# AVR28.net
KiCad netlist of a schematic drawn in EAGLE
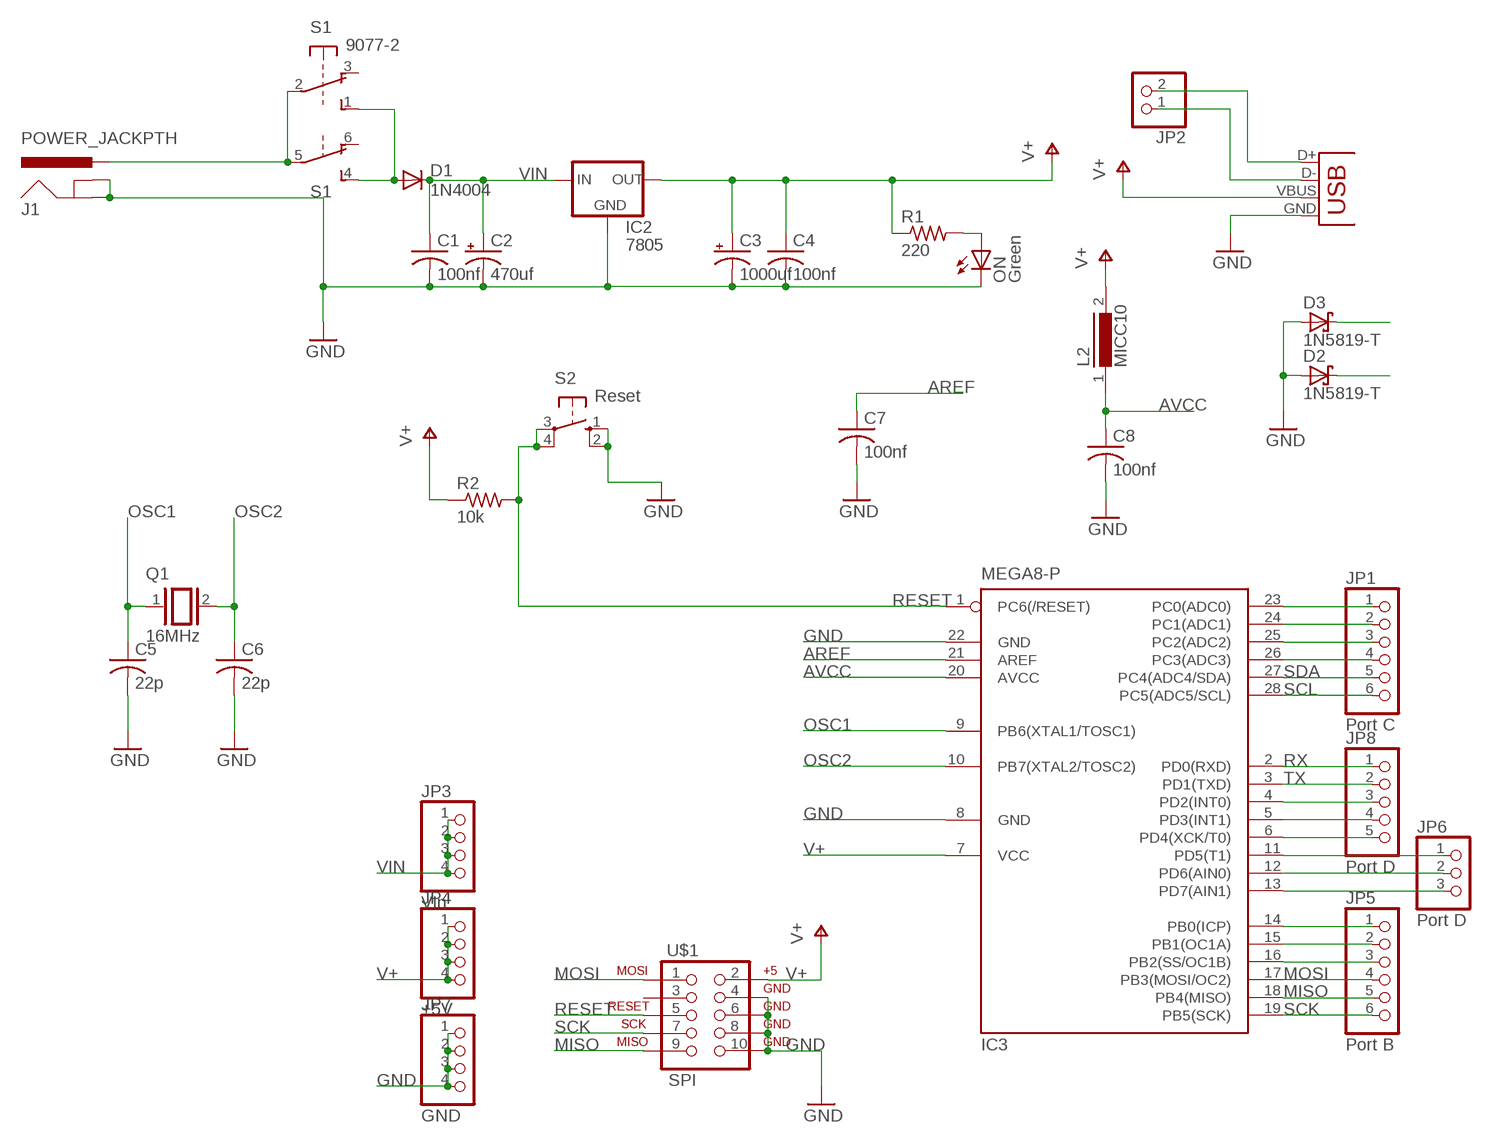
[diagram p0: schematic, sheet 1]

(export (version "E")
  (design (tool "Eeschema 10.0.6"))
  (components
    (comp (ref "C1")
      (value "100nf")
      (footprint "eagle-import:C050-025X075")
      (libsource (lib "eagle-import") (part "C-US050-025X075"))
    )
    (comp (ref "C2")
      (value "470uf")
      (footprint "eagle-import:E3,5-8")
      (libsource (lib "eagle-import") (part "CPOL-USE3.5-8"))
    )
    (comp (ref "C3")
      (value "1000uf")
      (footprint "eagle-import:E3,5-8")
      (libsource (lib "eagle-import") (part "CPOL-USE3.5-8"))
    )
    (comp (ref "C4")
      (value "100nf")
      (footprint "eagle-import:C050-025X075")
      (libsource (lib "eagle-import") (part "C-US050-025X075"))
    )
    (comp (ref "C5")
      (value "22p")
      (footprint "eagle-import:C050-025X075")
      (libsource (lib "eagle-import") (part "C-US050-025X075"))
    )
    (comp (ref "C6")
      (value "22p")
      (footprint "eagle-import:C050-025X075")
      (libsource (lib "eagle-import") (part "C-US050-025X075"))
    )
    (comp (ref "C7")
      (value "100nf")
      (footprint "eagle-import:C050-025X075")
      (libsource (lib "eagle-import") (part "C-US050-025X075"))
    )
    (comp (ref "C8")
      (value "100nf")
      (footprint "eagle-import:C050-025X075")
      (libsource (lib "eagle-import") (part "C-US050-025X075"))
    )
    (comp (ref "D1")
      (value "1N4004")
      (footprint "eagle-import:DO41-10")
      (libsource (lib "eagle-import") (part "1N4004"))
    )
    (comp (ref "D2")
      (value "1N5819-T")
      (footprint "eagle-import:DO41-7.6")
      (libsource (lib "eagle-import") (part "1N5819-T"))
    )
    (comp (ref "D3")
      (value "1N5819-T")
      (footprint "eagle-import:DO41-7.6")
      (libsource (lib "eagle-import") (part "1N5819-T"))
    )
    (comp (ref "IC2")
      (value "7805")
      (footprint "eagle-import:78XXL")
      (libsource (lib "eagle-import") (part "V_REG_78XXSIDE"))
    )
    (comp (ref "IC3")
      (value "MEGA8-P")
      (footprint "eagle-import:DIL28-3")
      (libsource (lib "eagle-import") (part "MEGA8-P"))
    )
    (comp (ref "J1")
      (value "POWER_JACKPTH")
      (footprint "eagle-import:POWER_JACK_PTH")
      (libsource (lib "eagle-import") (part "POWER_JACKPTH"))
    )
    (comp (ref "JP1")
      (value "Port C")
      (footprint "eagle-import:1X06")
      (libsource (lib "eagle-import") (part "PINHD-1X6"))
    )
    (comp (ref "JP2")
      (value "PINHD-1X2")
      (footprint "eagle-import:1X02")
      (libsource (lib "eagle-import") (part "PINHD-1X2"))
    )
    (comp (ref "JP3")
      (value "VIn")
      (footprint "eagle-import:1X04")
      (libsource (lib "eagle-import") (part "PINHD-1X4"))
    )
    (comp (ref "JP4")
      (value "+5V")
      (footprint "eagle-import:1X04")
      (libsource (lib "eagle-import") (part "PINHD-1X4"))
    )
    (comp (ref "JP5")
      (value "Port B")
      (footprint "eagle-import:1X06")
      (libsource (lib "eagle-import") (part "PINHD-1X6"))
    )
    (comp (ref "JP6")
      (value "Port D")
      (footprint "eagle-import:1X03")
      (libsource (lib "eagle-import") (part "PINHD-1X3"))
    )
    (comp (ref "JP7")
      (value "GND")
      (footprint "eagle-import:1X04")
      (libsource (lib "eagle-import") (part "PINHD-1X4"))
    )
    (comp (ref "JP8")
      (value "Port D")
      (footprint "eagle-import:1X05")
      (libsource (lib "eagle-import") (part "PINHD-1X5"))
    )
    (comp (ref "L2")
      (value "MICC10")
      (footprint "eagle-import:MICC10")
      (libsource (lib "eagle-import") (part "MICC10"))
    )
    (comp (ref "ON")
      (value "Green")
      (footprint "eagle-import:LED3MM")
      (libsource (lib "eagle-import") (part "LED3MM"))
    )
    (comp (ref "Q1")
      (value "16MHz")
      (footprint "eagle-import:QS")
      (libsource (lib "eagle-import") (part "XTAL/S"))
    )
    (comp (ref "R1")
      (value "220")
      (footprint "eagle-import:0207_10")
      (libsource (lib "eagle-import") (part "R-US_0207/10"))
    )
    (comp (ref "R2")
      (value "10k")
      (footprint "eagle-import:0207_10")
      (libsource (lib "eagle-import") (part "R-US_0207/10"))
    )
    (comp (ref "S1")
      (value "9077-2")
      (footprint "eagle-import:9077-2")
      (libsource (lib "eagle-import") (part "9077-2"))
    )
    (comp (ref "S2")
      (value "Reset")
      (footprint "eagle-import:B3F-10XX")
      (fields (field (name "MPN") "B3F-1000"))
      (libsource (lib "eagle-import") (part "10-XX"))
    )
    (comp (ref "U$1")
      (value "SPI")
      (footprint "eagle-import:2X5-SHROUDED_LOCK")
      (libsource (lib "eagle-import") (part "AVR_SPI_PROG2LOCK"))
    )
    (comp (ref "X1")
      (value "USBPTH")
      (footprint "eagle-import:USB-B-PTH")
      (libsource (lib "eagle-import") (part "USBPTH"))
    )
  )
  (nets
    (net (code "1") (name "/AREF") (class "Default")
      (node (ref "C7") (pin "1") (pinfunction "1_1") (pintype "passive"))
      (node (ref "IC3") (pin "21") (pinfunction "AREF_21") (pintype "passive"))
    )
    (net (code "2") (name "/AVCC") (class "Default")
      (node (ref "C8") (pin "1") (pinfunction "1_1") (pintype "passive"))
      (node (ref "IC3") (pin "20") (pinfunction "AVCC_20") (pintype "power_in"))
      (node (ref "L2") (pin "1") (pinfunction "1_1") (pintype "passive"))
    )
    (net (code "3") (name "/D+") (class "Default")
      (node (ref "D2") (pin "C") (pinfunction "C_C") (pintype "passive"))
      (node (ref "JP2") (pin "2") (pinfunction "2_2") (pintype "passive"))
      (node (ref "X1") (pin "D+") (pinfunction "D+_D+") (pintype "bidirectional"))
    )
    (net (code "4") (name "/D-") (class "Default")
      (node (ref "D3") (pin "C") (pinfunction "C_C") (pintype "passive"))
      (node (ref "JP2") (pin "1") (pinfunction "1_1") (pintype "passive"))
      (node (ref "X1") (pin "D-") (pinfunction "D-_D-") (pintype "bidirectional"))
    )
    (net (code "5") (name "/MISO") (class "Default")
      (node (ref "IC3") (pin "18") (pinfunction "PB4(MISO)_18") (pintype "bidirectional"))
      (node (ref "JP5") (pin "5") (pinfunction "5_5") (pintype "passive"))
      (node (ref "U$1") (pin "9") (pinfunction "9_9") (pintype "passive"))
    )
    (net (code "6") (name "/MOSI") (class "Default")
      (node (ref "IC3") (pin "17") (pinfunction "PB3(MOSI/OC2)_17") (pintype "bidirectional"))
      (node (ref "JP5") (pin "4") (pinfunction "4_4") (pintype "passive"))
      (node (ref "U$1") (pin "1") (pinfunction "1_1") (pintype "passive"))
    )
    (net (code "7") (name "/OSC1") (class "Default")
      (node (ref "C5") (pin "1") (pinfunction "1_1") (pintype "passive"))
      (node (ref "IC3") (pin "9") (pinfunction "PB6(XTAL1/TOSC1)_9") (pintype "bidirectional"))
      (node (ref "Q1") (pin "1") (pinfunction "1_1") (pintype "passive"))
    )
    (net (code "8") (name "/OSC2") (class "Default")
      (node (ref "C6") (pin "1") (pinfunction "1_1") (pintype "passive"))
      (node (ref "IC3") (pin "10") (pinfunction "PB7(XTAL2/TOSC2)_10") (pintype "bidirectional"))
      (node (ref "Q1") (pin "2") (pinfunction "2_2") (pintype "passive"))
    )
    (net (code "9") (name "/RESET") (class "Default")
      (node (ref "IC3") (pin "1") (pinfunction "PC6(/RESET)_1") (pintype "bidirectional"))
      (node (ref "R2") (pin "2") (pinfunction "2_2") (pintype "passive"))
      (node (ref "S2") (pin "3") (pinfunction "P_3") (pintype "passive"))
      (node (ref "S2") (pin "4") (pinfunction "P1_4") (pintype "passive"))
      (node (ref "U$1") (pin "5") (pinfunction "5_5") (pintype "passive"))
    )
    (net (code "10") (name "/RX") (class "Default")
      (node (ref "IC3") (pin "2") (pinfunction "PD0(RXD)_2") (pintype "bidirectional"))
      (node (ref "JP8") (pin "1") (pinfunction "1_1") (pintype "passive"))
    )
    (net (code "11") (name "/SCK") (class "Default")
      (node (ref "IC3") (pin "19") (pinfunction "PB5(SCK)_19") (pintype "bidirectional"))
      (node (ref "JP5") (pin "6") (pinfunction "6_6") (pintype "passive"))
      (node (ref "U$1") (pin "7") (pinfunction "7_7") (pintype "passive"))
    )
    (net (code "12") (name "/SCL") (class "Default")
      (node (ref "IC3") (pin "28") (pinfunction "PC5(ADC5/SCL)_28") (pintype "bidirectional"))
      (node (ref "JP1") (pin "6") (pinfunction "6_6") (pintype "passive"))
    )
    (net (code "13") (name "/SDA") (class "Default")
      (node (ref "IC3") (pin "27") (pinfunction "PC4(ADC4/SDA)_27") (pintype "bidirectional"))
      (node (ref "JP1") (pin "5") (pinfunction "5_5") (pintype "passive"))
    )
    (net (code "14") (name "/TX") (class "Default")
      (node (ref "IC3") (pin "3") (pinfunction "PD1(TXD)_3") (pintype "bidirectional"))
      (node (ref "JP8") (pin "2") (pinfunction "2_2") (pintype "passive"))
    )
    (net (code "15") (name "/VIN") (class "Default")
      (node (ref "C1") (pin "1") (pinfunction "1_1") (pintype "passive"))
      (node (ref "C2") (pin "+") (pinfunction "+_+") (pintype "passive"))
      (node (ref "D1") (pin "C") (pinfunction "C_C") (pintype "passive"))
      (node (ref "IC2") (pin "IN") (pinfunction "IN_IN") (pintype "input"))
      (node (ref "JP3") (pin "1") (pinfunction "1_1") (pintype "passive"))
      (node (ref "JP3") (pin "2") (pinfunction "2_2") (pintype "passive"))
      (node (ref "JP3") (pin "3") (pinfunction "3_3") (pintype "passive"))
      (node (ref "JP3") (pin "4") (pinfunction "4_4") (pintype "passive"))
    )
    (net (code "16") (name "GND") (class "Default")
      (node (ref "C1") (pin "2") (pinfunction "2_2") (pintype "passive"))
      (node (ref "C2") (pin "-") (pinfunction "-_-") (pintype "passive"))
      (node (ref "C3") (pin "-") (pinfunction "-_-") (pintype "passive"))
      (node (ref "C4") (pin "2") (pinfunction "2_2") (pintype "passive"))
      (node (ref "C5") (pin "2") (pinfunction "2_2") (pintype "passive"))
      (node (ref "C6") (pin "2") (pinfunction "2_2") (pintype "passive"))
      (node (ref "C7") (pin "2") (pinfunction "2_2") (pintype "passive"))
      (node (ref "C8") (pin "2") (pinfunction "2_2") (pintype "passive"))
      (node (ref "D2") (pin "A") (pinfunction "A_A") (pintype "passive"))
      (node (ref "D3") (pin "A") (pinfunction "A_A") (pintype "passive"))
      (node (ref "IC2") (pin "GND") (pinfunction "GND_GND") (pintype "input"))
      (node (ref "IC3") (pin "22") (pinfunction "GND_22") (pintype "power_in"))
      (node (ref "IC3") (pin "8") (pinfunction "GND_8") (pintype "power_in"))
      (node (ref "J1") (pin "GND") (pinfunction "GND_GND") (pintype "bidirectional"))
      (node (ref "J1") (pin "GNDBREAK") (pinfunction "GNDBREAK_GNDBREAK") (pintype "bidirectional"))
      (node (ref "JP7") (pin "1") (pinfunction "1_1") (pintype "passive"))
      (node (ref "JP7") (pin "2") (pinfunction "2_2") (pintype "passive"))
      (node (ref "JP7") (pin "3") (pinfunction "3_3") (pintype "passive"))
      (node (ref "JP7") (pin "4") (pinfunction "4_4") (pintype "passive"))
      (node (ref "ON") (pin "K") (pinfunction "C_K") (pintype "passive"))
      (node (ref "S2") (pin "1") (pinfunction "S_1") (pintype "passive"))
      (node (ref "S2") (pin "2") (pinfunction "S1_2") (pintype "passive"))
      (node (ref "U$1") (pin "10") (pinfunction "10_10") (pintype "passive"))
      (node (ref "U$1") (pin "4") (pinfunction "4_4") (pintype "passive"))
      (node (ref "U$1") (pin "6") (pinfunction "6_6") (pintype "passive"))
      (node (ref "U$1") (pin "8") (pinfunction "8_8") (pintype "passive"))
      (node (ref "X1") (pin "GND") (pinfunction "GND_GND") (pintype "bidirectional"))
    )
    (net (code "17") (name "Net-(IC3-PB0(ICP))") (class "Default")
      (node (ref "IC3") (pin "14") (pinfunction "PB0(ICP)_14") (pintype "bidirectional"))
      (node (ref "JP5") (pin "1") (pinfunction "1_1") (pintype "passive"))
    )
    (net (code "18") (name "Net-(IC3-PB1(OC1A))") (class "Default")
      (node (ref "IC3") (pin "15") (pinfunction "PB1(OC1A)_15") (pintype "bidirectional"))
      (node (ref "JP5") (pin "2") (pinfunction "2_2") (pintype "passive"))
    )
    (net (code "19") (name "Net-(IC3-PB2(SS{slash}OC1B))") (class "Default")
      (node (ref "IC3") (pin "16") (pinfunction "PB2(SS/OC1B)_16") (pintype "bidirectional"))
      (node (ref "JP5") (pin "3") (pinfunction "3_3") (pintype "passive"))
    )
    (net (code "20") (name "Net-(IC3-PC0(ADC0))") (class "Default")
      (node (ref "IC3") (pin "23") (pinfunction "PC0(ADC0)_23") (pintype "bidirectional"))
      (node (ref "JP1") (pin "1") (pinfunction "1_1") (pintype "passive"))
    )
    (net (code "21") (name "Net-(IC3-PC1(ADC1))") (class "Default")
      (node (ref "IC3") (pin "24") (pinfunction "PC1(ADC1)_24") (pintype "bidirectional"))
      (node (ref "JP1") (pin "2") (pinfunction "2_2") (pintype "passive"))
    )
    (net (code "22") (name "Net-(IC3-PC2(ADC2))") (class "Default")
      (node (ref "IC3") (pin "25") (pinfunction "PC2(ADC2)_25") (pintype "bidirectional"))
      (node (ref "JP1") (pin "3") (pinfunction "3_3") (pintype "passive"))
    )
    (net (code "23") (name "Net-(IC3-PC3(ADC3))") (class "Default")
      (node (ref "IC3") (pin "26") (pinfunction "PC3(ADC3)_26") (pintype "bidirectional"))
      (node (ref "JP1") (pin "4") (pinfunction "4_4") (pintype "passive"))
    )
    (net (code "24") (name "Net-(IC3-PD2(INT0))") (class "Default")
      (node (ref "IC3") (pin "4") (pinfunction "PD2(INT0)_4") (pintype "bidirectional"))
      (node (ref "JP8") (pin "3") (pinfunction "3_3") (pintype "passive"))
    )
    (net (code "25") (name "Net-(IC3-PD3(INT1))") (class "Default")
      (node (ref "IC3") (pin "5") (pinfunction "PD3(INT1)_5") (pintype "bidirectional"))
      (node (ref "JP8") (pin "4") (pinfunction "4_4") (pintype "passive"))
    )
    (net (code "26") (name "Net-(IC3-PD4(XCK{slash}T0))") (class "Default")
      (node (ref "IC3") (pin "6") (pinfunction "PD4(XCK/T0)_6") (pintype "bidirectional"))
      (node (ref "JP8") (pin "5") (pinfunction "5_5") (pintype "passive"))
    )
    (net (code "27") (name "Net-(IC3-PD5(T1))") (class "Default")
      (node (ref "IC3") (pin "11") (pinfunction "PD5(T1)_11") (pintype "bidirectional"))
      (node (ref "JP6") (pin "1") (pinfunction "1_1") (pintype "passive"))
    )
    (net (code "28") (name "Net-(IC3-PD6(AIN0))") (class "Default")
      (node (ref "IC3") (pin "12") (pinfunction "PD6(AIN0)_12") (pintype "bidirectional"))
      (node (ref "JP6") (pin "2") (pinfunction "2_2") (pintype "passive"))
    )
    (net (code "29") (name "Net-(IC3-PD7(AIN1))") (class "Default")
      (node (ref "IC3") (pin "13") (pinfunction "PD7(AIN1)_13") (pintype "bidirectional"))
      (node (ref "JP6") (pin "3") (pinfunction "3_3") (pintype "passive"))
    )
    (net (code "30") (name "Net-(ON-PadA)") (class "Default")
      (node (ref "ON") (pin "A") (pinfunction "A_A") (pintype "passive"))
      (node (ref "R1") (pin "2") (pinfunction "2_2") (pintype "passive"))
    )
    (net (code "31") (name "Net-(S1A-P)") (class "Default")
      (node (ref "J1") (pin "PWR") (pinfunction "PWR_PWR") (pintype "bidirectional"))
      (node (ref "S1") (pin "2") (pinfunction "P_2") (pintype "passive"))
      (node (ref "S1") (pin "5") (pinfunction "P_5") (pintype "passive"))
    )
    (net (code "32") (name "Net-(S1A-S)") (class "Default")
      (node (ref "D1") (pin "A") (pinfunction "A_A") (pintype "passive"))
      (node (ref "S1") (pin "1") (pinfunction "S_1") (pintype "passive"))
      (node (ref "S1") (pin "4") (pinfunction "S_4") (pintype "passive"))
    )
    (net (code "33") (name "V+") (class "Default")
      (node (ref "C3") (pin "+") (pinfunction "+_+") (pintype "passive"))
      (node (ref "C4") (pin "1") (pinfunction "1_1") (pintype "passive"))
      (node (ref "IC2") (pin "OUT") (pinfunction "OUT_OUT") (pintype "output"))
      (node (ref "IC3") (pin "7") (pinfunction "VCC_7") (pintype "power_in"))
      (node (ref "JP4") (pin "1") (pinfunction "1_1") (pintype "passive"))
      (node (ref "JP4") (pin "2") (pinfunction "2_2") (pintype "passive"))
      (node (ref "JP4") (pin "3") (pinfunction "3_3") (pintype "passive"))
      (node (ref "JP4") (pin "4") (pinfunction "4_4") (pintype "passive"))
      (node (ref "L2") (pin "2") (pinfunction "2_2") (pintype "passive"))
      (node (ref "R1") (pin "1") (pinfunction "1_1") (pintype "passive"))
      (node (ref "R2") (pin "1") (pinfunction "1_1") (pintype "passive"))
      (node (ref "U$1") (pin "2") (pinfunction "2_2") (pintype "passive"))
      (node (ref "X1") (pin "VBUS") (pinfunction "VBUS_VBUS") (pintype "bidirectional"))
    )
    (net (code "34") (name "unconnected-(S1A-O-Pad3)") (class "Default")
      (node (ref "S1") (pin "3") (pinfunction "O_3") (pintype "passive"))
    )
    (net (code "35") (name "unconnected-(S1B-O-Pad6)") (class "Default")
      (node (ref "S1") (pin "6") (pinfunction "O_6") (pintype "passive"))
    )
    (net (code "36") (name "unconnected-(U$1-Pad3)") (class "Default")
      (node (ref "U$1") (pin "3") (pinfunction "3_3") (pintype "passive"))
    )
  )
)
